# 006_FPGA_DDRII.net
KiCad netlist of a schematic drawn in Altium Designer
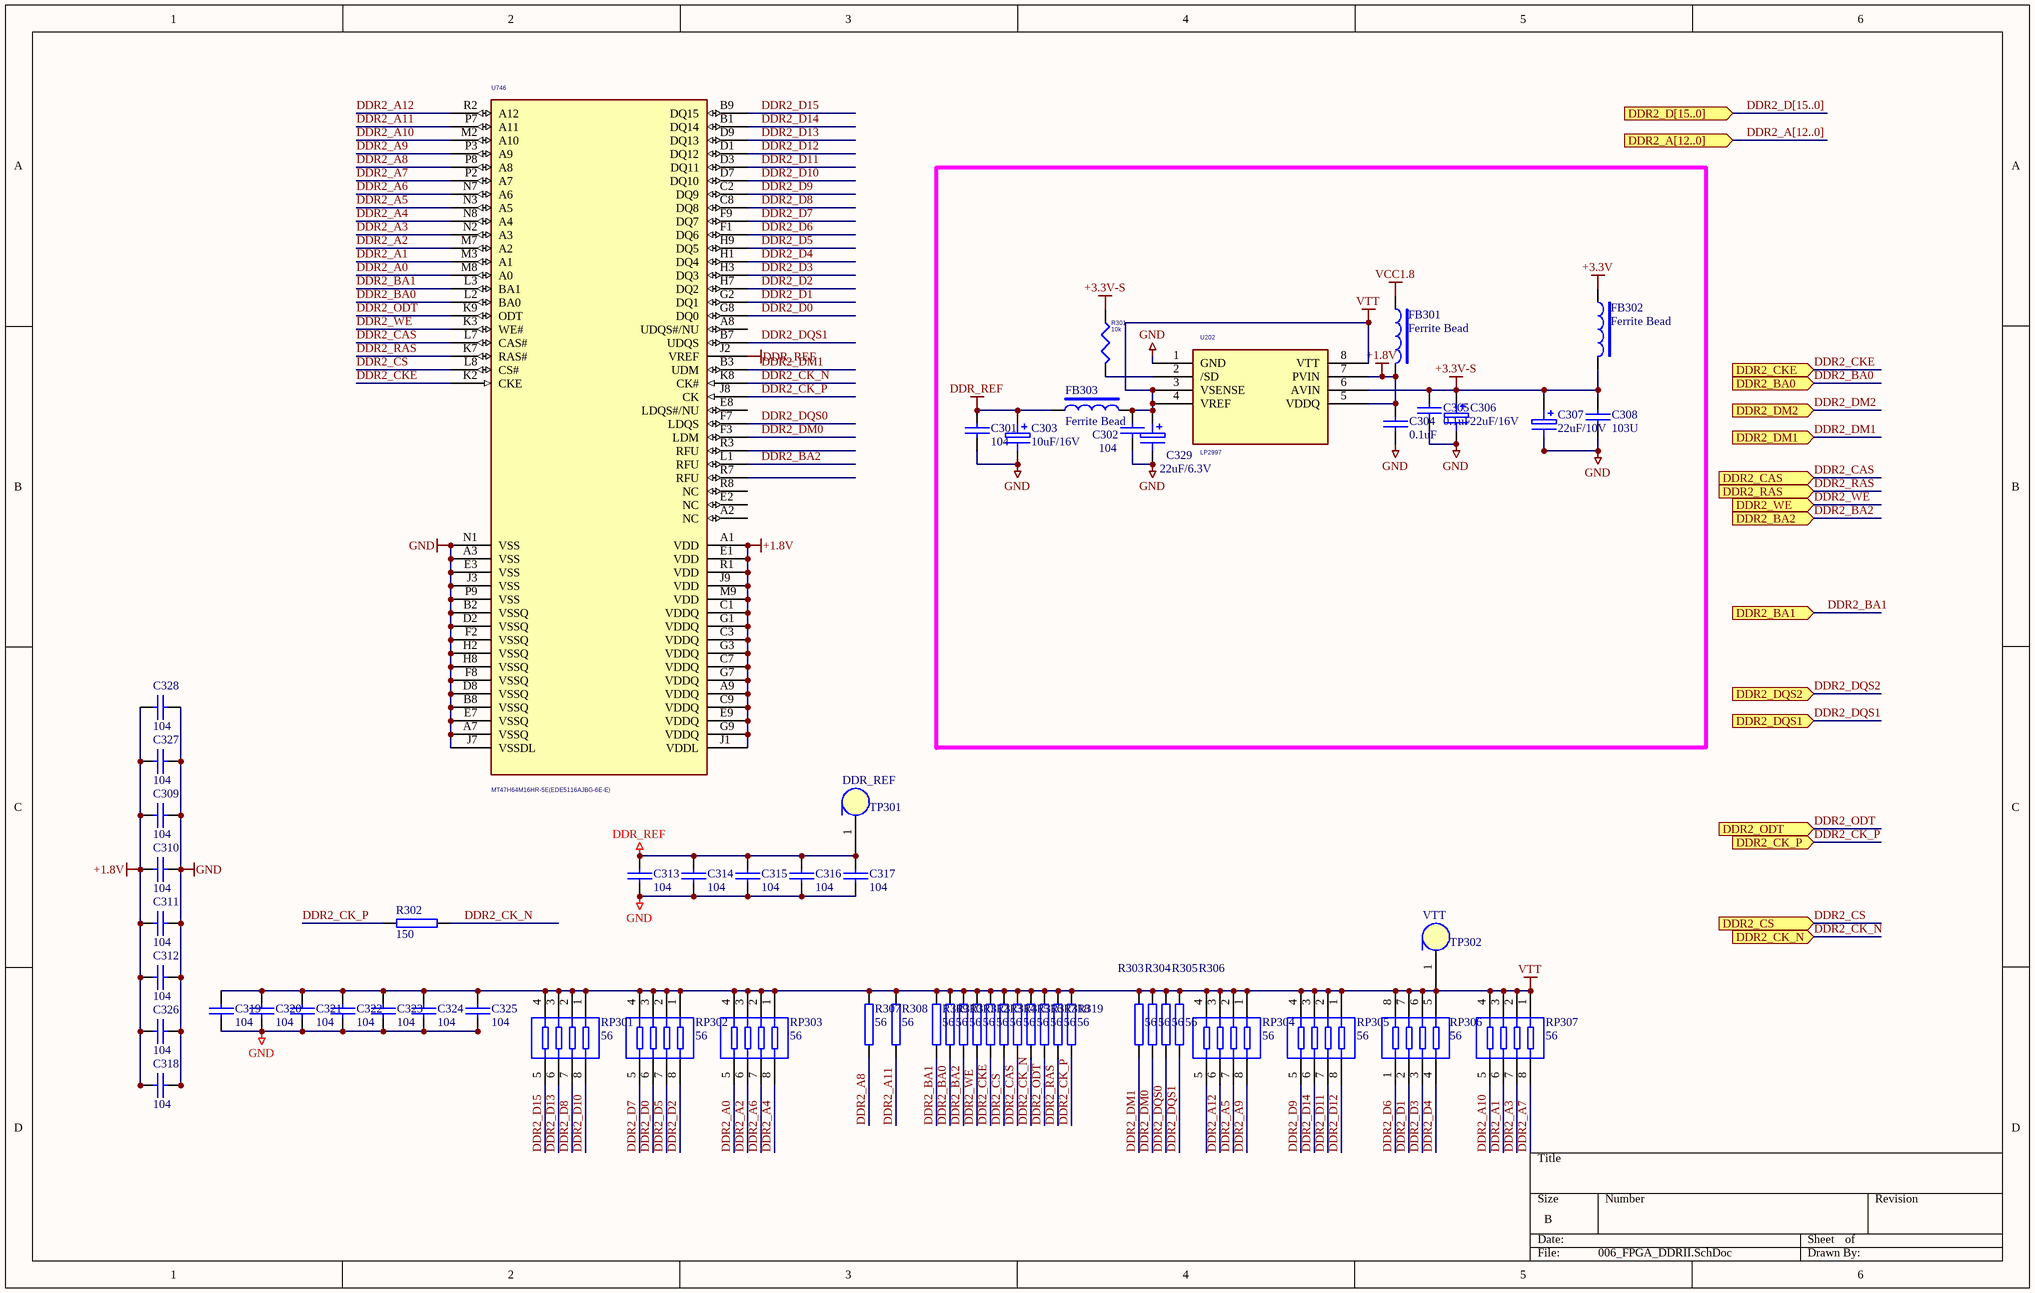
[diagram p0: 006_FPGA_DDRII.SchDoc]

(export (version "E")
  (design (tool "Eeschema 10.0.6"))
  (components
    (comp (ref "C301")
      (value "104")
      (footprint "C0402")
      (description "Capacitor")
      (libsource (lib "*") (part "CAP"))
    )
    (comp (ref "C302")
      (value "104")
      (footprint "C0402")
      (description "Capacitor")
      (libsource (lib "*") (part "CAP"))
    )
    (comp (ref "C303") (value "10uF/16V") (footprint "C3528") (libsource (lib "*") (part "ELECTRO1")))
    (comp (ref "C304") (value "0.1uF") (footprint "C0402") (libsource (lib "") (part "CAP_1")))
    (comp (ref "C305") (value "0.1uF") (footprint "C0402") (libsource (lib "") (part "CAP_1")))
    (comp (ref "C306") (value "22uF/16V") (footprint "C3528") (libsource (lib "*") (part "ELECTRO1")))
    (comp (ref "C307") (value "22uF/10V") (footprint "C3528") (libsource (lib "*") (part "ELECTRO1")))
    (comp (ref "C308") (value "103U") (footprint "C0402") (libsource (lib "") (part "CAP_1")))
    (comp (ref "C309")
      (value "104")
      (footprint "C0402")
      (description "Capacitor")
      (libsource (lib "*") (part "CAP"))
    )
    (comp (ref "C310")
      (value "104")
      (footprint "C0402")
      (description "Capacitor")
      (libsource (lib "*") (part "CAP"))
    )
    (comp (ref "C311")
      (value "104")
      (footprint "C0402")
      (description "Capacitor")
      (libsource (lib "*") (part "CAP"))
    )
    (comp (ref "C312")
      (value "104")
      (footprint "C0402")
      (description "Capacitor")
      (libsource (lib "*") (part "CAP"))
    )
    (comp (ref "C313")
      (value "104")
      (footprint "C0402")
      (description "Capacitor")
      (libsource (lib "*") (part "CAP"))
    )
    (comp (ref "C314")
      (value "104")
      (footprint "C0402")
      (description "Capacitor")
      (libsource (lib "*") (part "CAP"))
    )
    (comp (ref "C315")
      (value "104")
      (footprint "C0402")
      (description "Capacitor")
      (libsource (lib "*") (part "CAP"))
    )
    (comp (ref "C316")
      (value "104")
      (footprint "C0402")
      (description "Capacitor")
      (libsource (lib "*") (part "CAP"))
    )
    (comp (ref "C317")
      (value "104")
      (footprint "C0402")
      (description "Capacitor")
      (libsource (lib "*") (part "CAP"))
    )
    (comp (ref "C318")
      (value "104")
      (footprint "C0402")
      (description "Capacitor")
      (libsource (lib "*") (part "CAP"))
    )
    (comp (ref "C319")
      (value "104")
      (footprint "C0402")
      (description "Capacitor")
      (libsource (lib "*") (part "CAP"))
    )
    (comp (ref "C320")
      (value "104")
      (footprint "C0402")
      (description "Capacitor")
      (libsource (lib "*") (part "CAP"))
    )
    (comp (ref "C321")
      (value "104")
      (footprint "C0402")
      (description "Capacitor")
      (libsource (lib "*") (part "CAP"))
    )
    (comp (ref "C322")
      (value "104")
      (footprint "C0402")
      (description "Capacitor")
      (libsource (lib "*") (part "CAP"))
    )
    (comp (ref "C323")
      (value "104")
      (footprint "C0402")
      (description "Capacitor")
      (libsource (lib "*") (part "CAP"))
    )
    (comp (ref "C324")
      (value "104")
      (footprint "C0402")
      (description "Capacitor")
      (libsource (lib "*") (part "CAP"))
    )
    (comp (ref "C325")
      (value "104")
      (footprint "C0402")
      (description "Capacitor")
      (libsource (lib "*") (part "CAP"))
    )
    (comp (ref "C326")
      (value "104")
      (footprint "C0402")
      (description "Capacitor")
      (libsource (lib "*") (part "CAP"))
    )
    (comp (ref "C327")
      (value "104")
      (footprint "C0402")
      (description "Capacitor")
      (libsource (lib "*") (part "CAP"))
    )
    (comp (ref "C328")
      (value "104")
      (footprint "C0402")
      (description "Capacitor")
      (libsource (lib "*") (part "CAP"))
    )
    (comp (ref "C329") (value "22uF/6.3V") (footprint "C3528") (libsource (lib "*") (part "ELECTRO1")))
    (comp (ref "FB301") (value "Ferrite Bead") (footprint "FB0805") (libsource (lib "*") (part "INDUCTOR2")))
    (comp (ref "FB302") (value "Ferrite Bead") (footprint "FB0805") (libsource (lib "*") (part "INDUCTOR2")))
    (comp (ref "FB303") (value "Ferrite Bead") (footprint "FB0805") (libsource (lib "") (part "INDUCTOR2_1")))
    (comp (ref "R301") (value "10k") (footprint "R0402") (libsource (lib "*") (part "R")))
    (comp (ref "R302") (value "150") (footprint "R0402") (libsource (lib "*") (part "RES2")))
    (comp (ref "R303") (value "56") (footprint "R0402") (libsource (lib "*") (part "RES2")))
    (comp (ref "R304") (value "56") (footprint "R0402") (libsource (lib "*") (part "RES2")))
    (comp (ref "R305") (value "56") (footprint "R0402") (libsource (lib "*") (part "RES2")))
    (comp (ref "R306") (value "56") (footprint "R0402") (libsource (lib "*") (part "RES2")))
    (comp (ref "R307") (value "56") (footprint "R0402") (libsource (lib "*") (part "RES2")))
    (comp (ref "R308") (value "56") (footprint "R0402") (libsource (lib "*") (part "RES2")))
    (comp (ref "R309") (value "56") (footprint "R0402") (libsource (lib "*") (part "RES2")))
    (comp (ref "R310") (value "56") (footprint "R0402") (libsource (lib "*") (part "RES2")))
    (comp (ref "R311") (value "56") (footprint "R0402") (libsource (lib "*") (part "RES2")))
    (comp (ref "R312") (value "56") (footprint "R0402") (libsource (lib "*") (part "RES2")))
    (comp (ref "R313") (value "56") (footprint "R0402") (libsource (lib "*") (part "RES2")))
    (comp (ref "R314") (value "56") (footprint "R0402") (libsource (lib "*") (part "RES2")))
    (comp (ref "R315") (value "56") (footprint "R0402") (libsource (lib "*") (part "RES2")))
    (comp (ref "R316") (value "56") (footprint "R0402") (libsource (lib "*") (part "RES2")))
    (comp (ref "R317") (value "56") (footprint "R0402") (libsource (lib "*") (part "RES2")))
    (comp (ref "R318") (value "56") (footprint "R0402") (libsource (lib "*") (part "RES2")))
    (comp (ref "R319") (value "56") (footprint "R0402") (libsource (lib "*") (part "RES2")))
    (comp (ref "RP301") (value "56") (footprint "RP0603") (libsource (lib "*") (part "RESPACK4")))
    (comp (ref "RP302") (value "56") (footprint "RP0603") (libsource (lib "*") (part "RESPACK4")))
    (comp (ref "RP303") (value "56") (footprint "RP0603") (libsource (lib "*") (part "RESPACK4")))
    (comp (ref "RP304") (value "56") (footprint "RP0603") (libsource (lib "*") (part "RESPACK4")))
    (comp (ref "RP305") (value "56") (footprint "RP0603") (libsource (lib "*") (part "RESPACK4")))
    (comp (ref "RP306") (value "56") (footprint "RP0603") (libsource (lib "*") (part "RESPACK4")))
    (comp (ref "RP307") (value "56") (footprint "RP0603") (libsource (lib "*") (part "RESPACK4")))
    (comp (ref "TP301") (value "DDR_REF") (footprint "PIN-TP2") (libsource (lib "*") (part "TP1")))
    (comp (ref "TP302") (value "VTT") (footprint "PIN-TP2") (libsource (lib "*") (part "TP1")))
    (comp (ref "U202") (value "LP2997") (footprint "SOIC8") (libsource (lib "*") (part "LP2997")))
    (comp (ref "U746")
      (value "MT47H64M16HR-5E(EDE5116AJBG-6E-E)")
      (footprint "BGA84-0.8")
      (libsource (lib "*") (part "EDE2516ABSE-6E-E"))
    )
  )
  (nets
    (net (code "1") (name "+1.8V") (class "Default")
      (node (ref "C304") (pin "2") (pintype "passive"))
      (node (ref "C309") (pin "1") (pinfunction "1_1") (pintype "passive"))
      (node (ref "C310") (pin "1") (pinfunction "1_1") (pintype "passive"))
      (node (ref "C311") (pin "1") (pinfunction "1_1") (pintype "passive"))
      (node (ref "C312") (pin "1") (pinfunction "1_1") (pintype "passive"))
      (node (ref "C318") (pin "1") (pinfunction "1_1") (pintype "passive"))
      (node (ref "C326") (pin "1") (pinfunction "1_1") (pintype "passive"))
      (node (ref "C327") (pin "1") (pinfunction "1_1") (pintype "passive"))
      (node (ref "C328") (pin "1") (pinfunction "1_1") (pintype "passive"))
      (node (ref "FB301") (pin "2") (pintype "passive"))
      (node (ref "U202") (pin "5") (pinfunction "VDDQ_5") (pintype "power_in"))
      (node (ref "U202") (pin "7") (pinfunction "PVIN_7") (pintype "power_in"))
      (node (ref "U746") (pin "A1") (pinfunction "VDD_A1") (pintype "power_in"))
      (node (ref "U746") (pin "A9") (pinfunction "VDDQ_A9") (pintype "power_in"))
      (node (ref "U746") (pin "C1") (pinfunction "VDDQ_C1") (pintype "power_in"))
      (node (ref "U746") (pin "C3") (pinfunction "VDDQ_C3") (pintype "power_in"))
      (node (ref "U746") (pin "C7") (pinfunction "VDDQ_C7") (pintype "power_in"))
      (node (ref "U746") (pin "C9") (pinfunction "VDDQ_C9") (pintype "power_in"))
      (node (ref "U746") (pin "E1") (pinfunction "VDD_E1") (pintype "power_in"))
      (node (ref "U746") (pin "E9") (pinfunction "VDDQ_E9") (pintype "power_in"))
      (node (ref "U746") (pin "G1") (pinfunction "VDDQ_G1") (pintype "power_in"))
      (node (ref "U746") (pin "G3") (pinfunction "VDDQ_G3") (pintype "power_in"))
      (node (ref "U746") (pin "G7") (pinfunction "VDDQ_G7") (pintype "power_in"))
      (node (ref "U746") (pin "G9") (pinfunction "VDDQ_G9") (pintype "power_in"))
      (node (ref "U746") (pin "J1") (pinfunction "VDDL_J1") (pintype "power_in"))
      (node (ref "U746") (pin "J9") (pinfunction "VDD_J9") (pintype "power_in"))
      (node (ref "U746") (pin "M9") (pinfunction "VDD_M9") (pintype "power_in"))
      (node (ref "U746") (pin "R1") (pinfunction "VDD_R1") (pintype "power_in"))
    )
    (net (code "2") (name "+3.3V") (class "Default") (node (ref "FB302") (pin "1") (pintype "passive")))
    (net (code "3") (name "+3.3V-S") (class "Default")
      (node (ref "C305") (pin "1") (pintype "passive"))
      (node (ref "C306") (pin "1") (pintype "passive"))
      (node (ref "C307") (pin "1") (pintype "passive"))
      (node (ref "C308") (pin "1") (pintype "passive"))
      (node (ref "FB302") (pin "2") (pintype "passive"))
      (node (ref "R301") (pin "1") (pinfunction "1_1") (pintype "passive"))
      (node (ref "U202") (pin "6") (pinfunction "AVIN_6") (pintype "power_in"))
    )
    (net (code "4") (name "/DDR2_A0") (class "Default")
      (node (ref "RP303") (pin "5") (pinfunction "5_5") (pintype "passive"))
      (node (ref "U746") (pin "M8") (pinfunction "A0_M8") (pintype "bidirectional"))
    )
    (net (code "5") (name "/DDR2_A1") (class "Default")
      (node (ref "RP307") (pin "6") (pinfunction "6_6") (pintype "passive"))
      (node (ref "U746") (pin "M3") (pinfunction "A1_M3") (pintype "bidirectional"))
    )
    (net (code "6") (name "/DDR2_A2") (class "Default")
      (node (ref "RP303") (pin "6") (pinfunction "6_6") (pintype "passive"))
      (node (ref "U746") (pin "M7") (pinfunction "A2_M7") (pintype "bidirectional"))
    )
    (net (code "7") (name "/DDR2_A3") (class "Default")
      (node (ref "RP307") (pin "7") (pinfunction "7_7") (pintype "passive"))
      (node (ref "U746") (pin "N2") (pinfunction "A3_N2") (pintype "bidirectional"))
    )
    (net (code "8") (name "/DDR2_A4") (class "Default")
      (node (ref "RP303") (pin "8") (pinfunction "8_8") (pintype "passive"))
      (node (ref "U746") (pin "N8") (pinfunction "A4_N8") (pintype "bidirectional"))
    )
    (net (code "9") (name "/DDR2_A5") (class "Default")
      (node (ref "RP304") (pin "7") (pinfunction "7_7") (pintype "passive"))
      (node (ref "U746") (pin "N3") (pinfunction "A5_N3") (pintype "bidirectional"))
    )
    (net (code "10") (name "/DDR2_A6") (class "Default")
      (node (ref "RP303") (pin "7") (pinfunction "7_7") (pintype "passive"))
      (node (ref "U746") (pin "N7") (pinfunction "A6_N7") (pintype "bidirectional"))
    )
    (net (code "11") (name "/DDR2_A7") (class "Default")
      (node (ref "RP307") (pin "8") (pinfunction "8_8") (pintype "passive"))
      (node (ref "U746") (pin "P2") (pinfunction "A7_P2") (pintype "bidirectional"))
    )
    (net (code "12") (name "/DDR2_A8") (class "Default")
      (node (ref "R307") (pin "1") (pintype "passive"))
      (node (ref "U746") (pin "P8") (pinfunction "A8_P8") (pintype "bidirectional"))
    )
    (net (code "13") (name "/DDR2_A9") (class "Default")
      (node (ref "RP304") (pin "8") (pinfunction "8_8") (pintype "passive"))
      (node (ref "U746") (pin "P3") (pinfunction "A9_P3") (pintype "bidirectional"))
    )
    (net (code "14") (name "/DDR2_A10") (class "Default")
      (node (ref "RP307") (pin "5") (pinfunction "5_5") (pintype "passive"))
      (node (ref "U746") (pin "M2") (pinfunction "A10_M2") (pintype "bidirectional"))
    )
    (net (code "15") (name "/DDR2_A11") (class "Default")
      (node (ref "R308") (pin "1") (pintype "passive"))
      (node (ref "U746") (pin "P7") (pinfunction "A11_P7") (pintype "bidirectional"))
    )
    (net (code "16") (name "/DDR2_A12") (class "Default")
      (node (ref "RP304") (pin "6") (pinfunction "6_6") (pintype "passive"))
      (node (ref "U746") (pin "R2") (pinfunction "A12_R2") (pintype "bidirectional"))
    )
    (net (code "18") (name "/DDR2_BA0") (class "Default")
      (node (ref "R310") (pin "1") (pintype "passive"))
      (node (ref "U746") (pin "L2") (pinfunction "BA0_L2") (pintype "bidirectional"))
    )
    (net (code "19") (name "/DDR2_BA1") (class "Default")
      (node (ref "R309") (pin "1") (pintype "passive"))
      (node (ref "U746") (pin "L3") (pinfunction "BA1_L3") (pintype "bidirectional"))
    )
    (net (code "20") (name "/DDR2_BA2") (class "Default")
      (node (ref "R311") (pin "1") (pintype "passive"))
      (node (ref "U746") (pin "L1") (pinfunction "RFU_L1") (pintype "bidirectional"))
    )
    (net (code "21") (name "/DDR2_CAS") (class "Default")
      (node (ref "R315") (pin "1") (pintype "passive"))
      (node (ref "U746") (pin "L7") (pinfunction "CAS#_L7") (pintype "bidirectional"))
    )
    (net (code "22") (name "/DDR2_CKE") (class "Default")
      (node (ref "R313") (pin "1") (pintype "passive"))
      (node (ref "U746") (pin "K2") (pinfunction "CKE_K2") (pintype "input"))
    )
    (net (code "23") (name "/DDR2_CK_N") (class "Default")
      (node (ref "R302") (pin "2") (pintype "passive"))
      (node (ref "R316") (pin "1") (pintype "passive"))
      (node (ref "U746") (pin "K8") (pinfunction "CK#_K8") (pintype "input"))
    )
    (net (code "24") (name "/DDR2_CK_P") (class "Default")
      (node (ref "R302") (pin "1") (pintype "passive"))
      (node (ref "R319") (pin "1") (pintype "passive"))
      (node (ref "U746") (pin "J8") (pinfunction "CK_J8") (pintype "input"))
    )
    (net (code "25") (name "/DDR2_CS") (class "Default")
      (node (ref "R314") (pin "1") (pintype "passive"))
      (node (ref "U746") (pin "L8") (pinfunction "CS#_L8") (pintype "bidirectional"))
    )
    (net (code "26") (name "/DDR2_D0") (class "Default")
      (node (ref "RP302") (pin "6") (pinfunction "6_6") (pintype "passive"))
      (node (ref "U746") (pin "G8") (pinfunction "DQ0_G8") (pintype "bidirectional"))
    )
    (net (code "27") (name "/DDR2_D1") (class "Default")
      (node (ref "RP306") (pin "2") (pinfunction "2_2") (pintype "passive"))
      (node (ref "U746") (pin "G2") (pinfunction "DQ1_G2") (pintype "bidirectional"))
    )
    (net (code "28") (name "/DDR2_D2") (class "Default")
      (node (ref "RP302") (pin "8") (pinfunction "8_8") (pintype "passive"))
      (node (ref "U746") (pin "H7") (pinfunction "DQ2_H7") (pintype "bidirectional"))
    )
    (net (code "29") (name "/DDR2_D3") (class "Default")
      (node (ref "RP306") (pin "3") (pinfunction "3_3") (pintype "passive"))
      (node (ref "U746") (pin "H3") (pinfunction "DQ3_H3") (pintype "bidirectional"))
    )
    (net (code "30") (name "/DDR2_D4") (class "Default")
      (node (ref "RP306") (pin "4") (pinfunction "4_4") (pintype "passive"))
      (node (ref "U746") (pin "H1") (pinfunction "DQ4_H1") (pintype "bidirectional"))
    )
    (net (code "31") (name "/DDR2_D5") (class "Default")
      (node (ref "RP302") (pin "7") (pinfunction "7_7") (pintype "passive"))
      (node (ref "U746") (pin "H9") (pinfunction "DQ5_H9") (pintype "bidirectional"))
    )
    (net (code "32") (name "/DDR2_D6") (class "Default")
      (node (ref "RP306") (pin "1") (pinfunction "1_1") (pintype "passive"))
      (node (ref "U746") (pin "F1") (pinfunction "DQ6_F1") (pintype "bidirectional"))
    )
    (net (code "33") (name "/DDR2_D7") (class "Default")
      (node (ref "RP302") (pin "5") (pinfunction "5_5") (pintype "passive"))
      (node (ref "U746") (pin "F9") (pinfunction "DQ7_F9") (pintype "bidirectional"))
    )
    (net (code "34") (name "/DDR2_D8") (class "Default")
      (node (ref "RP301") (pin "7") (pinfunction "7_7") (pintype "passive"))
      (node (ref "U746") (pin "C8") (pinfunction "DQ8_C8") (pintype "bidirectional"))
    )
    (net (code "35") (name "/DDR2_D9") (class "Default")
      (node (ref "RP305") (pin "5") (pinfunction "5_5") (pintype "passive"))
      (node (ref "U746") (pin "C2") (pinfunction "DQ9_C2") (pintype "bidirectional"))
    )
    (net (code "36") (name "/DDR2_D10") (class "Default")
      (node (ref "RP301") (pin "8") (pinfunction "8_8") (pintype "passive"))
      (node (ref "U746") (pin "D7") (pinfunction "DQ10_D7") (pintype "bidirectional"))
    )
    (net (code "37") (name "/DDR2_D11") (class "Default")
      (node (ref "RP305") (pin "7") (pinfunction "7_7") (pintype "passive"))
      (node (ref "U746") (pin "D3") (pinfunction "DQ11_D3") (pintype "bidirectional"))
    )
    (net (code "38") (name "/DDR2_D12") (class "Default")
      (node (ref "RP305") (pin "8") (pinfunction "8_8") (pintype "passive"))
      (node (ref "U746") (pin "D1") (pinfunction "DQ12_D1") (pintype "bidirectional"))
    )
    (net (code "39") (name "/DDR2_D13") (class "Default")
      (node (ref "RP301") (pin "6") (pinfunction "6_6") (pintype "passive"))
      (node (ref "U746") (pin "D9") (pinfunction "DQ13_D9") (pintype "bidirectional"))
    )
    (net (code "40") (name "/DDR2_D14") (class "Default")
      (node (ref "RP305") (pin "6") (pinfunction "6_6") (pintype "passive"))
      (node (ref "U746") (pin "B1") (pinfunction "DQ14_B1") (pintype "bidirectional"))
    )
    (net (code "41") (name "/DDR2_D15") (class "Default")
      (node (ref "RP301") (pin "5") (pinfunction "5_5") (pintype "passive"))
      (node (ref "U746") (pin "B9") (pinfunction "DQ15_B9") (pintype "bidirectional"))
    )
    (net (code "42") (name "/DDR2_DM0") (class "Default")
      (node (ref "R304") (pin "1") (pintype "passive"))
      (node (ref "U746") (pin "F3") (pinfunction "LDM_F3") (pintype "bidirectional"))
    )
    (net (code "43") (name "/DDR2_DM1") (class "Default")
      (node (ref "R303") (pin "1") (pintype "passive"))
      (node (ref "U746") (pin "B3") (pinfunction "UDM_B3") (pintype "bidirectional"))
    )
    (net (code "45") (name "/DDR2_DQS0") (class "Default")
      (node (ref "R305") (pin "1") (pintype "passive"))
      (node (ref "U746") (pin "F7") (pinfunction "LDQS_F7") (pintype "bidirectional"))
    )
    (net (code "46") (name "/DDR2_DQS1") (class "Default")
      (node (ref "R306") (pin "1") (pintype "passive"))
      (node (ref "U746") (pin "B7") (pinfunction "UDQS_B7") (pintype "bidirectional"))
    )
    (net (code "49") (name "/DDR2_ODT") (class "Default")
      (node (ref "R317") (pin "1") (pintype "passive"))
      (node (ref "U746") (pin "K9") (pinfunction "ODT_K9") (pintype "bidirectional"))
    )
    (net (code "50") (name "/DDR2_RAS") (class "Default")
      (node (ref "R318") (pin "1") (pintype "passive"))
      (node (ref "U746") (pin "K7") (pinfunction "RAS#_K7") (pintype "bidirectional"))
    )
    (net (code "51") (name "/DDR2_WE") (class "Default")
      (node (ref "R312") (pin "1") (pintype "passive"))
      (node (ref "U746") (pin "K3") (pinfunction "WE#_K3") (pintype "bidirectional"))
    )
    (net (code "52") (name "DDR_REF") (class "Default")
      (node (ref "C301") (pin "2") (pinfunction "2_2") (pintype "passive"))
      (node (ref "C303") (pin "1") (pintype "passive"))
      (node (ref "C313") (pin "2") (pinfunction "2_2") (pintype "passive"))
      (node (ref "C314") (pin "2") (pinfunction "2_2") (pintype "passive"))
      (node (ref "C315") (pin "2") (pinfunction "2_2") (pintype "passive"))
      (node (ref "C316") (pin "2") (pinfunction "2_2") (pintype "passive"))
      (node (ref "C317") (pin "2") (pinfunction "2_2") (pintype "passive"))
      (node (ref "FB303") (pin "1") (pintype "passive"))
      (node (ref "TP301") (pin "1") (pinfunction "1_1") (pintype "passive"))
      (node (ref "U746") (pin "J2") (pinfunction "VREF_J2") (pintype "power_in"))
    )
    (net (code "53") (name "GND") (class "Default")
      (node (ref "C301") (pin "1") (pinfunction "1_1") (pintype "passive"))
      (node (ref "C302") (pin "1") (pinfunction "1_1") (pintype "passive"))
      (node (ref "C303") (pin "2") (pintype "passive"))
      (node (ref "C304") (pin "1") (pintype "passive"))
      (node (ref "C305") (pin "2") (pintype "passive"))
      (node (ref "C306") (pin "2") (pintype "passive"))
      (node (ref "C307") (pin "2") (pintype "passive"))
      (node (ref "C308") (pin "2") (pintype "passive"))
      (node (ref "C309") (pin "2") (pinfunction "2_2") (pintype "passive"))
      (node (ref "C310") (pin "2") (pinfunction "2_2") (pintype "passive"))
      (node (ref "C311") (pin "2") (pinfunction "2_2") (pintype "passive"))
      (node (ref "C312") (pin "2") (pinfunction "2_2") (pintype "passive"))
      (node (ref "C313") (pin "1") (pinfunction "1_1") (pintype "passive"))
      (node (ref "C314") (pin "1") (pinfunction "1_1") (pintype "passive"))
      (node (ref "C315") (pin "1") (pinfunction "1_1") (pintype "passive"))
      (node (ref "C316") (pin "1") (pinfunction "1_1") (pintype "passive"))
      (node (ref "C317") (pin "1") (pinfunction "1_1") (pintype "passive"))
      (node (ref "C318") (pin "2") (pinfunction "2_2") (pintype "passive"))
      (node (ref "C319") (pin "1") (pinfunction "1_1") (pintype "passive"))
      (node (ref "C320") (pin "1") (pinfunction "1_1") (pintype "passive"))
      (node (ref "C321") (pin "1") (pinfunction "1_1") (pintype "passive"))
      (node (ref "C322") (pin "1") (pinfunction "1_1") (pintype "passive"))
      (node (ref "C323") (pin "1") (pinfunction "1_1") (pintype "passive"))
      (node (ref "C324") (pin "1") (pinfunction "1_1") (pintype "passive"))
      (node (ref "C325") (pin "1") (pinfunction "1_1") (pintype "passive"))
      (node (ref "C326") (pin "2") (pinfunction "2_2") (pintype "passive"))
      (node (ref "C327") (pin "2") (pinfunction "2_2") (pintype "passive"))
      (node (ref "C328") (pin "2") (pinfunction "2_2") (pintype "passive"))
      (node (ref "C329") (pin "2") (pintype "passive"))
      (node (ref "U202") (pin "1") (pinfunction "GND_1") (pintype "power_in"))
      (node (ref "U746") (pin "A3") (pinfunction "VSS_A3") (pintype "power_in"))
      (node (ref "U746") (pin "A7") (pinfunction "VSSQ_A7") (pintype "power_in"))
      (node (ref "U746") (pin "B2") (pinfunction "VSSQ_B2") (pintype "power_in"))
      (node (ref "U746") (pin "B8") (pinfunction "VSSQ_B8") (pintype "power_in"))
      (node (ref "U746") (pin "D2") (pinfunction "VSSQ_D2") (pintype "power_in"))
      (node (ref "U746") (pin "D8") (pinfunction "VSSQ_D8") (pintype "power_in"))
      (node (ref "U746") (pin "E3") (pinfunction "VSS_E3") (pintype "power_in"))
      (node (ref "U746") (pin "E7") (pinfunction "VSSQ_E7") (pintype "power_in"))
      (node (ref "U746") (pin "F2") (pinfunction "VSSQ_F2") (pintype "power_in"))
      (node (ref "U746") (pin "F8") (pinfunction "VSSQ_F8") (pintype "power_in"))
      (node (ref "U746") (pin "H2") (pinfunction "VSSQ_H2") (pintype "power_in"))
      (node (ref "U746") (pin "H8") (pinfunction "VSSQ_H8") (pintype "power_in"))
      (node (ref "U746") (pin "J3") (pinfunction "VSS_J3") (pintype "power_in"))
      (node (ref "U746") (pin "J7") (pinfunction "VSSDL_J7") (pintype "power_in"))
      (node (ref "U746") (pin "N1") (pinfunction "VSS_N1") (pintype "power_in"))
      (node (ref "U746") (pin "P9") (pinfunction "VSS_P9") (pintype "power_in"))
    )
    (net (code "54") (name "Net-(U202-{slash}SD)") (class "Default")
      (node (ref "R301") (pin "2") (pinfunction "2_2") (pintype "passive"))
      (node (ref "U202") (pin "2") (pinfunction "/SD_2") (pintype "passive"))
    )
    (net (code "55") (name "VCC1.8") (class "Default") (node (ref "FB301") (pin "1") (pintype "passive")))
    (net (code "56") (name "VTT") (class "Default")
      (node (ref "C302") (pin "2") (pinfunction "2_2") (pintype "passive"))
      (node (ref "C319") (pin "2") (pinfunction "2_2") (pintype "passive"))
      (node (ref "C320") (pin "2") (pinfunction "2_2") (pintype "passive"))
      (node (ref "C321") (pin "2") (pinfunction "2_2") (pintype "passive"))
      (node (ref "C322") (pin "2") (pinfunction "2_2") (pintype "passive"))
      (node (ref "C323") (pin "2") (pinfunction "2_2") (pintype "passive"))
      (node (ref "C324") (pin "2") (pinfunction "2_2") (pintype "passive"))
      (node (ref "C325") (pin "2") (pinfunction "2_2") (pintype "passive"))
      (node (ref "C329") (pin "1") (pintype "passive"))
      (node (ref "FB303") (pin "2") (pintype "passive"))
      (node (ref "R303") (pin "2") (pintype "passive"))
      (node (ref "R304") (pin "2") (pintype "passive"))
      (node (ref "R305") (pin "2") (pintype "passive"))
      (node (ref "R306") (pin "2") (pintype "passive"))
      (node (ref "R307") (pin "2") (pintype "passive"))
      (node (ref "R308") (pin "2") (pintype "passive"))
      (node (ref "R309") (pin "2") (pintype "passive"))
      (node (ref "R310") (pin "2") (pintype "passive"))
      (node (ref "R311") (pin "2") (pintype "passive"))
      (node (ref "R312") (pin "2") (pintype "passive"))
      (node (ref "R313") (pin "2") (pintype "passive"))
      (node (ref "R314") (pin "2") (pintype "passive"))
      (node (ref "R315") (pin "2") (pintype "passive"))
      (node (ref "R316") (pin "2") (pintype "passive"))
      (node (ref "R317") (pin "2") (pintype "passive"))
      (node (ref "R318") (pin "2") (pintype "passive"))
      (node (ref "R319") (pin "2") (pintype "passive"))
      (node (ref "RP301") (pin "1") (pinfunction "1_1") (pintype "passive"))
      (node (ref "RP301") (pin "2") (pinfunction "2_2") (pintype "passive"))
      (node (ref "RP301") (pin "3") (pinfunction "3_3") (pintype "passive"))
      (node (ref "RP301") (pin "4") (pinfunction "4_4") (pintype "passive"))
      (node (ref "RP302") (pin "1") (pinfunction "1_1") (pintype "passive"))
      (node (ref "RP302") (pin "2") (pinfunction "2_2") (pintype "passive"))
      (node (ref "RP302") (pin "3") (pinfunction "3_3") (pintype "passive"))
      (node (ref "RP302") (pin "4") (pinfunction "4_4") (pintype "passive"))
      (node (ref "RP303") (pin "1") (pinfunction "1_1") (pintype "passive"))
      (node (ref "RP303") (pin "2") (pinfunction "2_2") (pintype "passive"))
      (node (ref "RP303") (pin "3") (pinfunction "3_3") (pintype "passive"))
      (node (ref "RP303") (pin "4") (pinfunction "4_4") (pintype "passive"))
      (node (ref "RP304") (pin "1") (pinfunction "1_1") (pintype "passive"))
      (node (ref "RP304") (pin "2") (pinfunction "2_2") (pintype "passive"))
      (node (ref "RP304") (pin "3") (pinfunction "3_3") (pintype "passive"))
      (node (ref "RP304") (pin "4") (pinfunction "4_4") (pintype "passive"))
      (node (ref "RP305") (pin "1") (pinfunction "1_1") (pintype "passive"))
      (node (ref "RP305") (pin "2") (pinfunction "2_2") (pintype "passive"))
      (node (ref "RP305") (pin "3") (pinfunction "3_3") (pintype "passive"))
      (node (ref "RP305") (pin "4") (pinfunction "4_4") (pintype "passive"))
      (node (ref "RP306") (pin "5") (pinfunction "5_5") (pintype "passive"))
      (node (ref "RP306") (pin "6") (pinfunction "6_6") (pintype "passive"))
      (node (ref "RP306") (pin "7") (pinfunction "7_7") (pintype "passive"))
      (node (ref "RP306") (pin "8") (pinfunction "8_8") (pintype "passive"))
      (node (ref "RP307") (pin "1") (pinfunction "1_1") (pintype "passive"))
      (node (ref "RP307") (pin "2") (pinfunction "2_2") (pintype "passive"))
      (node (ref "RP307") (pin "3") (pinfunction "3_3") (pintype "passive"))
      (node (ref "RP307") (pin "4") (pinfunction "4_4") (pintype "passive"))
      (node (ref "TP302") (pin "1") (pinfunction "1_1") (pintype "passive"))
      (node (ref "U202") (pin "3") (pinfunction "VSENSE_3") (pintype "passive"))
      (node (ref "U202") (pin "4") (pinfunction "VREF_4") (pintype "power_in"))
      (node (ref "U202") (pin "8") (pinfunction "VTT_8") (pintype "power_in"))
    )
    (net (code "57") (name "unconnected-(RP304-Pad5)") (class "Default")
      (node (ref "RP304") (pin "5") (pinfunction "5_5") (pintype "passive"))
    )
    (net (code "58") (name "unconnected-(U746-LDQS#{slash}NU-PadE8)") (class "Default")
      (node (ref "U746") (pin "E8") (pinfunction "LDQS#/NU_E8") (pintype "bidirectional"))
    )
    (net (code "59") (name "unconnected-(U746-NC-PadA2)") (class "Default")
      (node (ref "U746") (pin "A2") (pinfunction "NC_A2") (pintype "bidirectional"))
    )
    (net (code "60") (name "unconnected-(U746-NC-PadE2)") (class "Default")
      (node (ref "U746") (pin "E2") (pinfunction "NC_E2") (pintype "bidirectional"))
    )
    (net (code "61") (name "unconnected-(U746-NC-PadR8)") (class "Default")
      (node (ref "U746") (pin "R8") (pinfunction "NC_R8") (pintype "bidirectional"))
    )
    (net (code "62") (name "unconnected-(U746-RFU-PadR3)") (class "Default")
      (node (ref "U746") (pin "R3") (pinfunction "RFU_R3") (pintype "bidirectional"))
    )
    (net (code "63") (name "unconnected-(U746-RFU-PadR7)") (class "Default")
      (node (ref "U746") (pin "R7") (pinfunction "RFU_R7") (pintype "bidirectional"))
    )
    (net (code "64") (name "unconnected-(U746-UDQS#{slash}NU-PadA8)") (class "Default")
      (node (ref "U746") (pin "A8") (pinfunction "UDQS#/NU_A8") (pintype "bidirectional"))
    )
  )
)
